# Remotor_1.net
KiCad netlist of a schematic drawn in Altium Designer
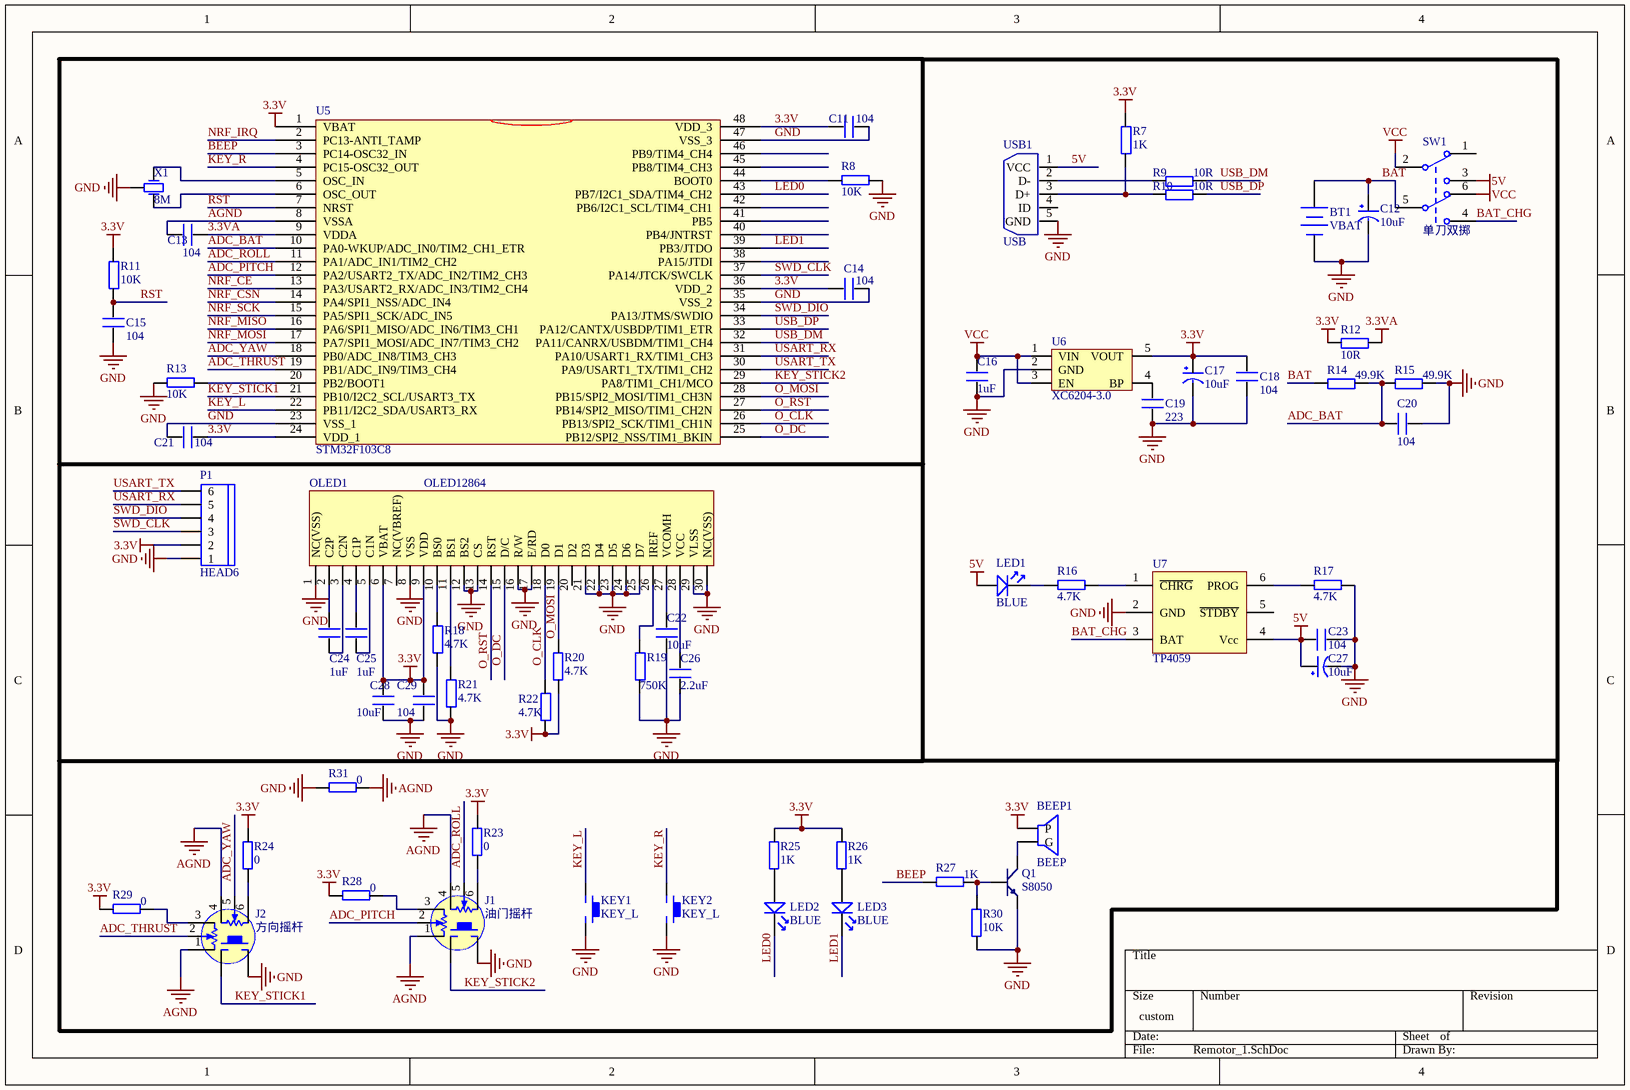
[diagram p0: Remotor_1.SchDoc]

(export (version "E")
  (design (tool "Eeschema 10.0.6"))
  (components
    (comp (ref "BEEP1") (value "BEEP") (footprint "BELL-5") (libsource (lib "REMOTOR V1.6") (part "BEEP")))
    (comp (ref "BT1")
      (value "VBAT")
      (footprint "BAT-2")
      (description "Multicell Battery")
      (fields (field (name "PUBLISHER") "Altium Limited"))
      (libsource (lib "REMOTOR V1.6") (part "Battery"))
    )
    (comp (ref "C11") (value "104") (footprint "0402") (libsource (lib "REMOTOR V1.6") (part "C")))
    (comp (ref "C12") (value "10uF") (footprint "C0805 钽电容") (libsource (lib "REMOTOR V1.6") (part "CAP")))
    (comp (ref "C13") (value "104") (footprint "0402") (libsource (lib "REMOTOR V1.6") (part "C")))
    (comp (ref "C14") (value "104") (footprint "0402") (libsource (lib "REMOTOR V1.6") (part "C")))
    (comp (ref "C15") (value "104") (footprint "0402") (libsource (lib "REMOTOR V1.6") (part "C")))
    (comp (ref "C16") (value "1uF") (footprint "0402") (libsource (lib "REMOTOR V1.6") (part "C")))
    (comp (ref "C17") (value "10uF") (footprint "C0805 钽电容") (libsource (lib "REMOTOR V1.6") (part "CAP")))
    (comp (ref "C18") (value "104") (footprint "0402") (libsource (lib "REMOTOR V1.6") (part "C")))
    (comp (ref "C19") (value "223") (footprint "0402") (libsource (lib "REMOTOR V1.6") (part "C")))
    (comp (ref "C20") (value "104") (footprint "0402") (libsource (lib "REMOTOR V1.6") (part "C")))
    (comp (ref "C21") (value "104") (footprint "0402") (libsource (lib "REMOTOR V1.6") (part "C")))
    (comp (ref "C22") (value "10uF") (footprint "0805") (libsource (lib "REMOTOR V1.6") (part "C")))
    (comp (ref "C23") (value "104") (footprint "0402") (libsource (lib "REMOTOR V1.6") (part "C")))
    (comp (ref "C24") (value "1uF") (footprint "0402") (libsource (lib "REMOTOR V1.6") (part "C")))
    (comp (ref "C25") (value "1uF") (footprint "0402") (libsource (lib "REMOTOR V1.6") (part "C")))
    (comp (ref "C26") (value "2.2uF") (footprint "0402") (libsource (lib "REMOTOR V1.6") (part "C")))
    (comp (ref "C27") (value "10uF") (footprint "C0805 钽电容") (libsource (lib "") (part "CAP_1")))
    (comp (ref "C28") (value "10uF") (footprint "0805") (libsource (lib "REMOTOR V1.6") (part "C")))
    (comp (ref "C29") (value "104") (footprint "0402") (libsource (lib "REMOTOR V1.6") (part "C")))
    (comp (ref "J1")
      (value "油门摇杆")
      (footprint "摇杆2")
      (description "摇杆")
      (libsource (lib "REMOTOR V1.6") (part "摇杆"))
    )
    (comp (ref "J2")
      (value "方向摇杆")
      (footprint "摇杆2")
      (description "摇杆")
      (libsource (lib "REMOTOR V1.6") (part "摇杆_1"))
    )
    (comp (ref "KEY1") (value "KEY_L") (footprint "KEY_M") (libsource (lib "REMOTOR V1.6") (part "KEY")))
    (comp (ref "KEY2") (value "KEY_L") (footprint "KEY_M") (libsource (lib "REMOTOR V1.6") (part "KEY")))
    (comp (ref "LED1") (value "BLUE") (footprint "0603") (libsource (lib "REMOTOR V1.6") (part "LED")))
    (comp (ref "LED2") (value "BLUE") (footprint "0603") (libsource (lib "REMOTOR V1.6") (part "LED")))
    (comp (ref "LED3") (value "BLUE") (footprint "0603") (libsource (lib "REMOTOR V1.6") (part "LED")))
    (comp (ref "OLED1")
      (value "OLED12864")
      (footprint "OLED_0.96")
      (libsource (lib "REMOTOR V1.6") (part "OLED12864"))
    )
    (comp (ref "P1") (value "HEAD6") (footprint "SH1.0-6P") (libsource (lib "REMOTOR V1.6") (part "HEAD6")))
    (comp (ref "Q1")
      (value "S8050")
      (footprint "SOT-23R")
      (description "8050/BCW846/BCW847")
      (libsource (lib "REMOTOR V1.6") (part "NPN"))
    )
    (comp (ref "R7") (value "1K") (footprint "0402") (libsource (lib "REMOTOR V1.6") (part "R")))
    (comp (ref "R8") (value "10K") (footprint "0402") (libsource (lib "REMOTOR V1.6") (part "R")))
    (comp (ref "R9") (value "10R") (footprint "0402") (libsource (lib "REMOTOR V1.6") (part "R")))
    (comp (ref "R10") (value "10R") (footprint "0402") (libsource (lib "REMOTOR V1.6") (part "R")))
    (comp (ref "R11") (value "10K") (footprint "0402") (libsource (lib "REMOTOR V1.6") (part "R")))
    (comp (ref "R12") (value "10R") (footprint "0402") (libsource (lib "REMOTOR V1.6") (part "R")))
    (comp (ref "R13") (value "10K") (footprint "0402") (libsource (lib "REMOTOR V1.6") (part "R")))
    (comp (ref "R14") (value "49.9K") (footprint "0402") (libsource (lib "REMOTOR V1.6") (part "R")))
    (comp (ref "R15") (value "49.9K") (footprint "0402") (libsource (lib "REMOTOR V1.6") (part "R")))
    (comp (ref "R16") (value "4.7K") (footprint "0402") (libsource (lib "REMOTOR V1.6") (part "R")))
    (comp (ref "R17") (value "4.7K") (footprint "0402") (libsource (lib "REMOTOR V1.6") (part "R")))
    (comp (ref "R18") (value "4.7K") (footprint "0402") (libsource (lib "REMOTOR V1.6") (part "R")))
    (comp (ref "R19") (value "750K") (footprint "0402") (libsource (lib "REMOTOR V1.6") (part "R")))
    (comp (ref "R20") (value "4.7K") (footprint "0402") (libsource (lib "REMOTOR V1.6") (part "R")))
    (comp (ref "R21") (value "4.7K") (footprint "0402") (libsource (lib "REMOTOR V1.6") (part "R")))
    (comp (ref "R22") (value "4.7K") (footprint "0402") (libsource (lib "REMOTOR V1.6") (part "R")))
    (comp (ref "R23") (value "0") (footprint "0402") (libsource (lib "REMOTOR V1.6") (part "R")))
    (comp (ref "R24") (value "0") (footprint "0402") (libsource (lib "REMOTOR V1.6") (part "R")))
    (comp (ref "R25") (value "1K") (footprint "0402") (libsource (lib "REMOTOR V1.6") (part "R")))
    (comp (ref "R26") (value "1K") (footprint "0402") (libsource (lib "REMOTOR V1.6") (part "R")))
    (comp (ref "R27") (value "1K") (footprint "0402") (libsource (lib "REMOTOR V1.6") (part "R")))
    (comp (ref "R28") (value "0") (footprint "0402") (libsource (lib "REMOTOR V1.6") (part "R")))
    (comp (ref "R29") (value "0") (footprint "0402") (libsource (lib "REMOTOR V1.6") (part "R")))
    (comp (ref "R30") (value "10K") (footprint "0402") (libsource (lib "REMOTOR V1.6") (part "R")))
    (comp (ref "R31") (value "0") (footprint "0402") (libsource (lib "REMOTOR V1.6") (part "R")))
    (comp (ref "SW1")
      (value "单刀双掷")
      (footprint "拨动开关DIP")
      (description "单刀双掷开关")
      (libsource (lib "REMOTOR V1.6") (part "单刀双掷开关"))
    )
    (comp (ref "U5")
      (value "STM32F103C8")
      (footprint "mTQFP48")
      (libsource (lib "REMOTOR V1.6") (part "STM32F103C6"))
    )
    (comp (ref "U6")
      (value "XC6204-3.0")
      (footprint "SOT-23-5")
      (description "3.3V超低压差LDO")
      (libsource (lib "REMOTOR V1.6") (part "RT9193-33"))
    )
    (comp (ref "U7")
      (value "TP4059")
      (footprint "SOT-23-6")
      (description "600mA充电芯片")
      (libsource (lib "REMOTOR V1.6") (part "TP2459"))
    )
    (comp (ref "USB1")
      (value "USB")
      (footprint "MICRO_USB5P_SOP")
      (libsource (lib "REMOTOR V1.6") (part "USB5"))
    )
    (comp (ref "X1") (value "8M") (footprint "XTAL3215") (libsource (lib "REMOTOR V1.6") (part "XTAL-3215")))
  )
  (nets
    (net (code "1") (name "/ADC_BAT") (class "Default")
      (node (ref "C20") (pin "1") (pintype "passive"))
      (node (ref "R14") (pin "2") (pintype "passive"))
      (node (ref "R15") (pin "1") (pintype "passive"))
      (node (ref "U5") (pin "10") (pinfunction "PA0-WKUP/ADC_IN0/TIM2_CH1_ETR_10") (pintype "passive"))
    )
    (net (code "2") (name "/ADC_PITCH") (class "Default")
      (node (ref "J1") (pin "2") (pinfunction "2_2") (pintype "passive"))
      (node (ref "U5") (pin "12") (pinfunction "PA2/USART2_TX/ADC_IN2/TIM2_CH3_12") (pintype "passive"))
    )
    (net (code "3") (name "/ADC_ROLL") (class "Default")
      (node (ref "J1") (pin "5") (pinfunction "5_5") (pintype "passive"))
      (node (ref "U5") (pin "11") (pinfunction "PA1/ADC_IN1/TIM2_CH2_11") (pintype "passive"))
    )
    (net (code "4") (name "/ADC_THRUST") (class "Default")
      (node (ref "J2") (pin "2") (pinfunction "2_2") (pintype "passive"))
      (node (ref "U5") (pin "19") (pinfunction "PB1/ADC_IN9/TIM3_CH4_19") (pintype "passive"))
    )
    (net (code "5") (name "/ADC_YAW") (class "Default")
      (node (ref "J2") (pin "5") (pinfunction "5_5") (pintype "passive"))
      (node (ref "U5") (pin "18") (pinfunction "PB0/ADC_IN8/TIM3_CH3_18") (pintype "passive"))
    )
    (net (code "6") (name "/BAT") (class "Default")
      (node (ref "BT1") (pin "1") (pinfunction "+_1") (pintype "passive"))
      (node (ref "C12") (pin "1") (pinfunction "VCC_1") (pintype "passive"))
      (node (ref "R14") (pin "1") (pintype "passive"))
      (node (ref "SW1") (pin "5") (pinfunction "5_5") (pintype "passive"))
    )
    (net (code "7") (name "/BAT_CHG") (class "Default")
      (node (ref "SW1") (pin "4") (pinfunction "4_4") (pintype "passive"))
      (node (ref "U7") (pin "3") (pinfunction "BAT_3") (pintype "passive"))
    )
    (net (code "8") (name "/BEEP") (class "Default")
      (node (ref "R27") (pin "2") (pintype "passive"))
      (node (ref "U5") (pin "3") (pinfunction "PC14-OSC32_IN_3") (pintype "passive"))
    )
    (net (code "9") (name "/KEY_L") (class "Default")
      (node (ref "KEY1") (pin "1") (pinfunction "1_1") (pintype "passive"))
      (node (ref "U5") (pin "22") (pinfunction "PB11/I2C2_SDA/USART3_RX_22") (pintype "passive"))
    )
    (net (code "10") (name "/KEY_R") (class "Default")
      (node (ref "KEY2") (pin "1") (pinfunction "1_1") (pintype "passive"))
      (node (ref "U5") (pin "4") (pinfunction "PC15-OSC32_OUT_4") (pintype "passive"))
    )
    (net (code "11") (name "/KEY_STICK1") (class "Default")
      (node (ref "J2") (pin "J2") (pinfunction "J2_J2") (pintype "passive"))
      (node (ref "U5") (pin "21") (pinfunction "PB10/I2C2_SCL/USART3_TX_21") (pintype "passive"))
    )
    (net (code "12") (name "/KEY_STICK2") (class "Default")
      (node (ref "J1") (pin "J2") (pinfunction "J2_J2") (pintype "passive"))
      (node (ref "U5") (pin "29") (pinfunction "PA8/TIM1_CH1/MCO_29") (pintype "passive"))
    )
    (net (code "13") (name "/LED0") (class "Default")
      (node (ref "LED2") (pin "2") (pinfunction "2_2") (pintype "passive"))
      (node (ref "U5") (pin "43") (pinfunction "PB7/I2C1_SDA/TIM4_CH2_43") (pintype "passive"))
    )
    (net (code "14") (name "/LED1") (class "Default")
      (node (ref "LED3") (pin "2") (pinfunction "2_2") (pintype "passive"))
      (node (ref "U5") (pin "39") (pinfunction "PB3/JTDO_39") (pintype "passive"))
    )
    (net (code "15") (name "/NRF_CE") (class "Default")
      (node (ref "U5") (pin "13") (pinfunction "PA3/USART2_RX/ADC_IN3/TIM2_CH4_13") (pintype "passive"))
    )
    (net (code "16") (name "/NRF_CSN") (class "Default")
      (node (ref "U5") (pin "14") (pinfunction "PA4/SPI1_NSS/ADC_IN4_14") (pintype "passive"))
    )
    (net (code "17") (name "/NRF_IRQ") (class "Default")
      (node (ref "U5") (pin "2") (pinfunction "PC13-ANTI_TAMP_2") (pintype "passive"))
    )
    (net (code "18") (name "/NRF_MISO") (class "Default")
      (node (ref "U5") (pin "16") (pinfunction "PA6/SPI1_MISO/ADC_IN6/TIM3_CH1_16") (pintype "passive"))
    )
    (net (code "19") (name "/NRF_MOSI") (class "Default")
      (node (ref "U5") (pin "17") (pinfunction "PA7/SPI1_MOSI/ADC_IN7/TIM3_CH2_17") (pintype "passive"))
    )
    (net (code "20") (name "/NRF_SCK") (class "Default")
      (node (ref "U5") (pin "15") (pinfunction "PA5/SPI1_SCK/ADC_IN5_15") (pintype "passive"))
    )
    (net (code "21") (name "/O_CLK") (class "Default")
      (node (ref "OLED1") (pin "18") (pinfunction "D0_18") (pintype "passive"))
      (node (ref "R22") (pin "2") (pintype "passive"))
      (node (ref "U5") (pin "26") (pinfunction "PB13/SPI2_SCK/TIM1_CH1N_26") (pintype "passive"))
    )
    (net (code "22") (name "/O_DC") (class "Default")
      (node (ref "OLED1") (pin "15") (pinfunction "D/C_15") (pintype "passive"))
      (node (ref "U5") (pin "25") (pinfunction "PB12/SPI2_NSS/TIM1_BKIN_25") (pintype "passive"))
    )
    (net (code "23") (name "/O_MOSI") (class "Default")
      (node (ref "OLED1") (pin "19") (pinfunction "D1_19") (pintype "passive"))
      (node (ref "R20") (pin "1") (pintype "passive"))
      (node (ref "U5") (pin "28") (pinfunction "PB15/SPI2_MOSI/TIM1_CH3N_28") (pintype "passive"))
    )
    (net (code "24") (name "/O_RST") (class "Default")
      (node (ref "OLED1") (pin "14") (pinfunction "RST_14") (pintype "passive"))
      (node (ref "U5") (pin "27") (pinfunction "PB14/SPI2_MISO/TIM1_CH2N_27") (pintype "passive"))
    )
    (net (code "25") (name "/RST") (class "Default")
      (node (ref "C15") (pin "2") (pintype "passive"))
      (node (ref "R11") (pin "1") (pintype "passive"))
      (node (ref "U5") (pin "7") (pinfunction "NRST_7") (pintype "passive"))
    )
    (net (code "26") (name "/SWD_CLK") (class "Default")
      (node (ref "P1") (pin "3") (pinfunction "3_3") (pintype "passive"))
      (node (ref "U5") (pin "37") (pinfunction "PA14/JTCK/SWCLK_37") (pintype "passive"))
    )
    (net (code "27") (name "/SWD_DIO") (class "Default")
      (node (ref "P1") (pin "4") (pinfunction "4_4") (pintype "passive"))
      (node (ref "U5") (pin "34") (pinfunction "PA13/JTMS/SWDIO_34") (pintype "passive"))
    )
    (net (code "28") (name "/USART_RX") (class "Default")
      (node (ref "P1") (pin "5") (pinfunction "5_5") (pintype "passive"))
      (node (ref "U5") (pin "31") (pinfunction "PA10/USART1_RX/TIM1_CH3_31") (pintype "passive"))
    )
    (net (code "29") (name "/USART_TX") (class "Default")
      (node (ref "P1") (pin "6") (pinfunction "6_6") (pintype "passive"))
      (node (ref "U5") (pin "30") (pinfunction "PA9/USART1_TX/TIM1_CH2_30") (pintype "passive"))
    )
    (net (code "30") (name "/USB_DM") (class "Default")
      (node (ref "R9") (pin "2") (pintype "passive"))
      (node (ref "U5") (pin "32") (pinfunction "PA11/CANRX/USBDM/TIM1_CH4_32") (pintype "passive"))
    )
    (net (code "31") (name "/USB_DP") (class "Default")
      (node (ref "R10") (pin "2") (pintype "passive"))
      (node (ref "U5") (pin "33") (pinfunction "PA12/CANTX/USBDP/TIM1_ETR_33") (pintype "passive"))
    )
    (net (code "32") (name "3.3V") (class "Default")
      (node (ref "BEEP1") (pin "1") (pinfunction "P_1") (pintype "passive"))
      (node (ref "C11") (pin "2") (pintype "passive"))
      (node (ref "C14") (pin "2") (pintype "passive"))
      (node (ref "C17") (pin "1") (pinfunction "VCC_1") (pintype "passive"))
      (node (ref "C18") (pin "2") (pintype "passive"))
      (node (ref "C21") (pin "1") (pintype "passive"))
      (node (ref "C28") (pin "2") (pintype "passive"))
      (node (ref "C29") (pin "2") (pintype "passive"))
      (node (ref "OLED1") (pin "6") (pinfunction "VBAT_6") (pintype "passive"))
      (node (ref "OLED1") (pin "9") (pinfunction "VDD_9") (pintype "passive"))
      (node (ref "P1") (pin "2") (pinfunction "2_2") (pintype "passive"))
      (node (ref "R11") (pin "2") (pintype "passive"))
      (node (ref "R12") (pin "1") (pintype "passive"))
      (node (ref "R20") (pin "2") (pintype "passive"))
      (node (ref "R22") (pin "1") (pintype "passive"))
      (node (ref "R23") (pin "1") (pintype "passive"))
      (node (ref "R24") (pin "1") (pintype "passive"))
      (node (ref "R25") (pin "1") (pintype "passive"))
      (node (ref "R26") (pin "1") (pintype "passive"))
      (node (ref "R28") (pin "2") (pintype "passive"))
      (node (ref "R29") (pin "2") (pintype "passive"))
      (node (ref "R7") (pin "2") (pintype "passive"))
      (node (ref "U5") (pin "1") (pinfunction "VBAT_1") (pintype "passive"))
      (node (ref "U5") (pin "24") (pinfunction "VDD_1_24") (pintype "passive"))
      (node (ref "U5") (pin "36") (pinfunction "VDD_2_36") (pintype "passive"))
      (node (ref "U5") (pin "48") (pinfunction "VDD_3_48") (pintype "passive"))
      (node (ref "U6") (pin "5") (pinfunction "VOUT_5") (pintype "passive"))
    )
    (net (code "33") (name "3.3VA") (class "Default")
      (node (ref "C13") (pin "2") (pintype "passive"))
      (node (ref "R12") (pin "2") (pintype "passive"))
      (node (ref "U5") (pin "9") (pinfunction "VDDA_9") (pintype "passive"))
    )
    (net (code "34") (name "5V") (class "Default")
      (node (ref "C23") (pin "2") (pintype "passive"))
      (node (ref "C27") (pin "1") (pinfunction "VCC_1") (pintype "passive"))
      (node (ref "LED1") (pin "1") (pinfunction "1_1") (pintype "passive"))
      (node (ref "SW1") (pin "3") (pinfunction "3_3") (pintype "passive"))
      (node (ref "U7") (pin "4") (pinfunction "Vcc_4") (pintype "passive"))
      (node (ref "USB1") (pin "1") (pinfunction "VCC_1") (pintype "passive"))
    )
    (net (code "35") (name "AGND") (class "Default")
      (node (ref "C13") (pin "1") (pintype "passive"))
      (node (ref "J1") (pin "1") (pinfunction "1_1") (pintype "passive"))
      (node (ref "J1") (pin "4") (pinfunction "4_4") (pintype "passive"))
      (node (ref "J2") (pin "1") (pinfunction "1_1") (pintype "passive"))
      (node (ref "J2") (pin "4") (pinfunction "4_4") (pintype "passive"))
      (node (ref "R31") (pin "1") (pintype "passive"))
      (node (ref "U5") (pin "8") (pinfunction "VSSA_8") (pintype "passive"))
    )
    (net (code "36") (name "GND") (class "Default")
      (node (ref "BT1") (pin "2") (pinfunction "-_2") (pintype "passive"))
      (node (ref "C11") (pin "1") (pintype "passive"))
      (node (ref "C12") (pin "2") (pinfunction "GND_2") (pintype "passive"))
      (node (ref "C14") (pin "1") (pintype "passive"))
      (node (ref "C15") (pin "1") (pintype "passive"))
      (node (ref "C16") (pin "1") (pintype "passive"))
      (node (ref "C17") (pin "2") (pinfunction "GND_2") (pintype "passive"))
      (node (ref "C18") (pin "1") (pintype "passive"))
      (node (ref "C19") (pin "1") (pintype "passive"))
      (node (ref "C20") (pin "2") (pintype "passive"))
      (node (ref "C21") (pin "2") (pintype "passive"))
      (node (ref "C22") (pin "1") (pintype "passive"))
      (node (ref "C23") (pin "1") (pintype "passive"))
      (node (ref "C26") (pin "1") (pintype "passive"))
      (node (ref "C27") (pin "2") (pinfunction "GND_2") (pintype "passive"))
      (node (ref "C28") (pin "1") (pintype "passive"))
      (node (ref "C29") (pin "1") (pintype "passive"))
      (node (ref "J1") (pin "J1") (pinfunction "J1_J1") (pintype "passive"))
      (node (ref "J2") (pin "J1") (pinfunction "J1_J1") (pintype "passive"))
      (node (ref "KEY1") (pin "2") (pinfunction "2_2") (pintype "passive"))
      (node (ref "KEY2") (pin "2") (pinfunction "2_2") (pintype "passive"))
      (node (ref "OLED1") (pin "1") (pinfunction "NC(VSS)_1") (pintype "passive"))
      (node (ref "OLED1") (pin "12") (pinfunction "BS2_12") (pintype "passive"))
      (node (ref "OLED1") (pin "13") (pinfunction "CS_13") (pintype "passive"))
      (node (ref "OLED1") (pin "16") (pinfunction "R/W_16") (pintype "passive"))
      (node (ref "OLED1") (pin "17") (pinfunction "E/RD_17") (pintype "passive"))
      (node (ref "OLED1") (pin "21") (pinfunction "D3_21") (pintype "passive"))
      (node (ref "OLED1") (pin "22") (pinfunction "D4_22") (pintype "passive"))
      (node (ref "OLED1") (pin "23") (pinfunction "D5_23") (pintype "passive"))
      (node (ref "OLED1") (pin "24") (pinfunction "D6_24") (pintype "passive"))
      (node (ref "OLED1") (pin "25") (pinfunction "D7_25") (pintype "passive"))
      (node (ref "OLED1") (pin "29") (pinfunction "VLSS_29") (pintype "passive"))
      (node (ref "OLED1") (pin "30") (pinfunction "NC(VSS)_30") (pintype "passive"))
      (node (ref "OLED1") (pin "8") (pinfunction "VSS_8") (pintype "passive"))
      (node (ref "P1") (pin "1") (pinfunction "1_1") (pintype "passive"))
      (node (ref "Q1") (pin "1") (pinfunction "E_1") (pintype "passive"))
      (node (ref "R13") (pin "2") (pintype "passive"))
      (node (ref "R15") (pin "2") (pintype "passive"))
      (node (ref "R17") (pin "1") (pintype "passive"))
      (node (ref "R18") (pin "1") (pintype "passive"))
      (node (ref "R19") (pin "1") (pintype "passive"))
      (node (ref "R21") (pin "1") (pintype "passive"))
      (node (ref "R30") (pin "2") (pintype "passive"))
      (node (ref "R31") (pin "2") (pintype "passive"))
      (node (ref "R8") (pin "1") (pintype "passive"))
      (node (ref "U5") (pin "23") (pinfunction "VSS_1_23") (pintype "passive"))
      (node (ref "U5") (pin "35") (pinfunction "VSS_2_35") (pintype "passive"))
      (node (ref "U5") (pin "47") (pinfunction "VSS_3_47") (pintype "passive"))
      (node (ref "U6") (pin "2") (pinfunction "GND_2") (pintype "passive"))
      (node (ref "U7") (pin "2") (pinfunction "GND_2") (pintype "passive"))
      (node (ref "USB1") (pin "5") (pinfunction "GND_5") (pintype "passive"))
      (node (ref "X1") (pin "2") (pinfunction "GND_2") (pintype "passive"))
    )
    (net (code "37") (name "Net-(BEEP1-G)") (class "Default")
      (node (ref "BEEP1") (pin "2") (pinfunction "G_2") (pintype "passive"))
      (node (ref "Q1") (pin "3") (pinfunction "C_3") (pintype "passive"))
    )
    (net (code "38") (name "Net-(J1-Pad3)") (class "Default")
      (node (ref "J1") (pin "3") (pinfunction "3_3") (pintype "passive"))
      (node (ref "R28") (pin "1") (pintype "passive"))
    )
    (net (code "39") (name "Net-(J1-Pad6)") (class "Default")
      (node (ref "J1") (pin "6") (pinfunction "6_6") (pintype "passive"))
      (node (ref "R23") (pin "2") (pintype "passive"))
    )
    (net (code "40") (name "Net-(J2-Pad3)") (class "Default")
      (node (ref "J2") (pin "3") (pinfunction "3_3") (pintype "passive"))
      (node (ref "R29") (pin "1") (pintype "passive"))
    )
    (net (code "41") (name "Net-(J2-Pad6)") (class "Default")
      (node (ref "J2") (pin "6") (pinfunction "6_6") (pintype "passive"))
      (node (ref "R24") (pin "2") (pintype "passive"))
    )
    (net (code "42") (name "Net-(LED1-Pad2)") (class "Default")
      (node (ref "LED1") (pin "2") (pinfunction "2_2") (pintype "passive"))
      (node (ref "R16") (pin "2") (pintype "passive"))
    )
    (net (code "43") (name "Net-(LED2-Pad1)") (class "Default")
      (node (ref "LED2") (pin "1") (pinfunction "1_1") (pintype "passive"))
      (node (ref "R25") (pin "2") (pintype "passive"))
    )
    (net (code "44") (name "Net-(LED3-Pad1)") (class "Default")
      (node (ref "LED3") (pin "1") (pinfunction "1_1") (pintype "passive"))
      (node (ref "R26") (pin "2") (pintype "passive"))
    )
    (net (code "45") (name "Net-(OLED1-BS0)") (class "Default")
      (node (ref "OLED1") (pin "10") (pinfunction "BS0_10") (pintype "passive"))
      (node (ref "R18") (pin "2") (pintype "passive"))
    )
    (net (code "46") (name "Net-(OLED1-BS1)") (class "Default")
      (node (ref "OLED1") (pin "11") (pinfunction "BS1_11") (pintype "passive"))
      (node (ref "R21") (pin "2") (pintype "passive"))
    )
    (net (code "47") (name "Net-(OLED1-C1N)") (class "Default")
      (node (ref "C25") (pin "1") (pintype "passive"))
      (node (ref "OLED1") (pin "5") (pinfunction "C1N_5") (pintype "passive"))
    )
    (net (code "48") (name "Net-(OLED1-C1P)") (class "Default")
      (node (ref "C25") (pin "2") (pintype "passive"))
      (node (ref "OLED1") (pin "4") (pinfunction "C1P_4") (pintype "passive"))
    )
    (net (code "49") (name "Net-(OLED1-C2N)") (class "Default")
      (node (ref "C24") (pin "1") (pintype "passive"))
      (node (ref "OLED1") (pin "3") (pinfunction "C2N_3") (pintype "passive"))
    )
    (net (code "50") (name "Net-(OLED1-C2P)") (class "Default")
      (node (ref "C24") (pin "2") (pintype "passive"))
      (node (ref "OLED1") (pin "2") (pinfunction "C2P_2") (pintype "passive"))
    )
    (net (code "51") (name "Net-(OLED1-IREF)") (class "Default")
      (node (ref "OLED1") (pin "26") (pinfunction "IREF_26") (pintype "passive"))
      (node (ref "R19") (pin "2") (pintype "passive"))
    )
    (net (code "52") (name "Net-(OLED1-VCC)") (class "Default")
      (node (ref "C26") (pin "2") (pintype "passive"))
      (node (ref "OLED1") (pin "28") (pinfunction "VCC_28") (pintype "passive"))
    )
    (net (code "53") (name "Net-(OLED1-VCOMH)") (class "Default")
      (node (ref "C22") (pin "2") (pintype "passive"))
      (node (ref "OLED1") (pin "27") (pinfunction "VCOMH_27") (pintype "passive"))
    )
    (net (code "54") (name "Net-(Q1-B)") (class "Default")
      (node (ref "Q1") (pin "2") (pinfunction "B_2") (pintype "passive"))
      (node (ref "R27") (pin "1") (pintype "passive"))
      (node (ref "R30") (pin "1") (pintype "passive"))
    )
    (net (code "55") (name "Net-(U5-BOOT0)") (class "Default")
      (node (ref "R8") (pin "2") (pintype "passive"))
      (node (ref "U5") (pin "44") (pinfunction "BOOT0_44") (pintype "passive"))
    )
    (net (code "56") (name "Net-(U5-OSC_IN)") (class "Default")
      (node (ref "U5") (pin "5") (pinfunction "OSC_IN_5") (pintype "passive"))
      (node (ref "X1") (pin "1") (pinfunction "OSC1_1") (pintype "passive"))
    )
    (net (code "57") (name "Net-(U5-OSC_OUT)") (class "Default")
      (node (ref "U5") (pin "6") (pinfunction "OSC_OUT_6") (pintype "passive"))
      (node (ref "X1") (pin "3") (pinfunction "OSC2_3") (pintype "passive"))
    )
    (net (code "58") (name "Net-(U5-PB2{slash}BOOT1)") (class "Default")
      (node (ref "R13") (pin "1") (pintype "passive"))
      (node (ref "U5") (pin "20") (pinfunction "PB2/BOOT1_20") (pintype "passive"))
    )
    (net (code "59") (name "Net-(U6-BP)") (class "Default")
      (node (ref "C19") (pin "2") (pintype "passive"))
      (node (ref "U6") (pin "4") (pinfunction "BP_4") (pintype "passive"))
    )
    (net (code "60") (name "Net-(U7-PROG)") (class "Default")
      (node (ref "R17") (pin "2") (pintype "passive"))
      (node (ref "U7") (pin "6") (pinfunction "PROG_6") (pintype "passive"))
    )
    (net (code "61") (name "Net-(U7-~{CHRG})") (class "Default")
      (node (ref "R16") (pin "1") (pintype "passive"))
      (node (ref "U7") (pin "1") (pinfunction "~{CHRG}_1") (pintype "passive"))
    )
    (net (code "62") (name "Net-(USB1-D+)") (class "Default")
      (node (ref "R10") (pin "1") (pintype "passive"))
      (node (ref "R7") (pin "1") (pintype "passive"))
      (node (ref "USB1") (pin "3") (pinfunction "D+_3") (pintype "passive"))
    )
    (net (code "63") (name "Net-(USB1-D-)") (class "Default")
      (node (ref "R9") (pin "1") (pintype "passive"))
      (node (ref "USB1") (pin "2") (pinfunction "D-_2") (pintype "passive"))
    )
    (net (code "64") (name "VCC") (class "Default")
      (node (ref "C16") (pin "2") (pintype "passive"))
      (node (ref "SW1") (pin "2") (pinfunction "2_2") (pintype "passive"))
      (node (ref "SW1") (pin "6") (pinfunction "6_6") (pintype "passive"))
      (node (ref "U6") (pin "1") (pinfunction "VIN_1") (pintype "passive"))
      (node (ref "U6") (pin "3") (pinfunction "EN_3") (pintype "passive"))
    )
    (net (code "65") (name "unconnected-(OLED1-D2-Pad20)") (class "Default")
      (node (ref "OLED1") (pin "20") (pinfunction "D2_20") (pintype "passive"))
    )
    (net (code "66") (name "unconnected-(OLED1-NC(VBREF)-Pad7)") (class "Default")
      (node (ref "OLED1") (pin "7") (pinfunction "NC(VBREF)_7") (pintype "passive"))
    )
    (net (code "67") (name "unconnected-(SW1-Pad1)") (class "Default")
      (node (ref "SW1") (pin "1") (pinfunction "1_1") (pintype "passive"))
    )
    (net (code "68") (name "unconnected-(U5-PA15{slash}JTDI-Pad38)") (class "Default")
      (node (ref "U5") (pin "38") (pinfunction "PA15/JTDI_38") (pintype "passive"))
    )
    (net (code "69") (name "unconnected-(U5-PB4{slash}JNTRST-Pad40)") (class "Default")
      (node (ref "U5") (pin "40") (pinfunction "PB4/JNTRST_40") (pintype "passive"))
    )
    (net (code "70") (name "unconnected-(U5-PB5-Pad41)") (class "Default")
      (node (ref "U5") (pin "41") (pinfunction "PB5_41") (pintype "passive"))
    )
    (net (code "71") (name "unconnected-(U5-PB6{slash}I2C1_SCL{slash}TIM4_CH1-Pad42)") (class "Default")
      (node (ref "U5") (pin "42") (pinfunction "PB6/I2C1_SCL/TIM4_CH1_42") (pintype "passive"))
    )
    (net (code "72") (name "unconnected-(U5-PB8{slash}TIM4_CH3-Pad45)") (class "Default")
      (node (ref "U5") (pin "45") (pinfunction "PB8/TIM4_CH3_45") (pintype "passive"))
    )
    (net (code "73") (name "unconnected-(U5-PB9{slash}TIM4_CH4-Pad46)") (class "Default")
      (node (ref "U5") (pin "46") (pinfunction "PB9/TIM4_CH4_46") (pintype "passive"))
    )
    (net (code "74") (name "unconnected-(U7-~{STDBY}-Pad5)") (class "Default")
      (node (ref "U7") (pin "5") (pinfunction "~{STDBY}_5") (pintype "passive"))
    )
    (net (code "75") (name "unconnected-(USB1-ID-Pad4)") (class "Default")
      (node (ref "USB1") (pin "4") (pinfunction "ID_4") (pintype "passive"))
    )
  )
)
